# Sheet1.net
KiCad netlist of a schematic drawn in Altium Designer
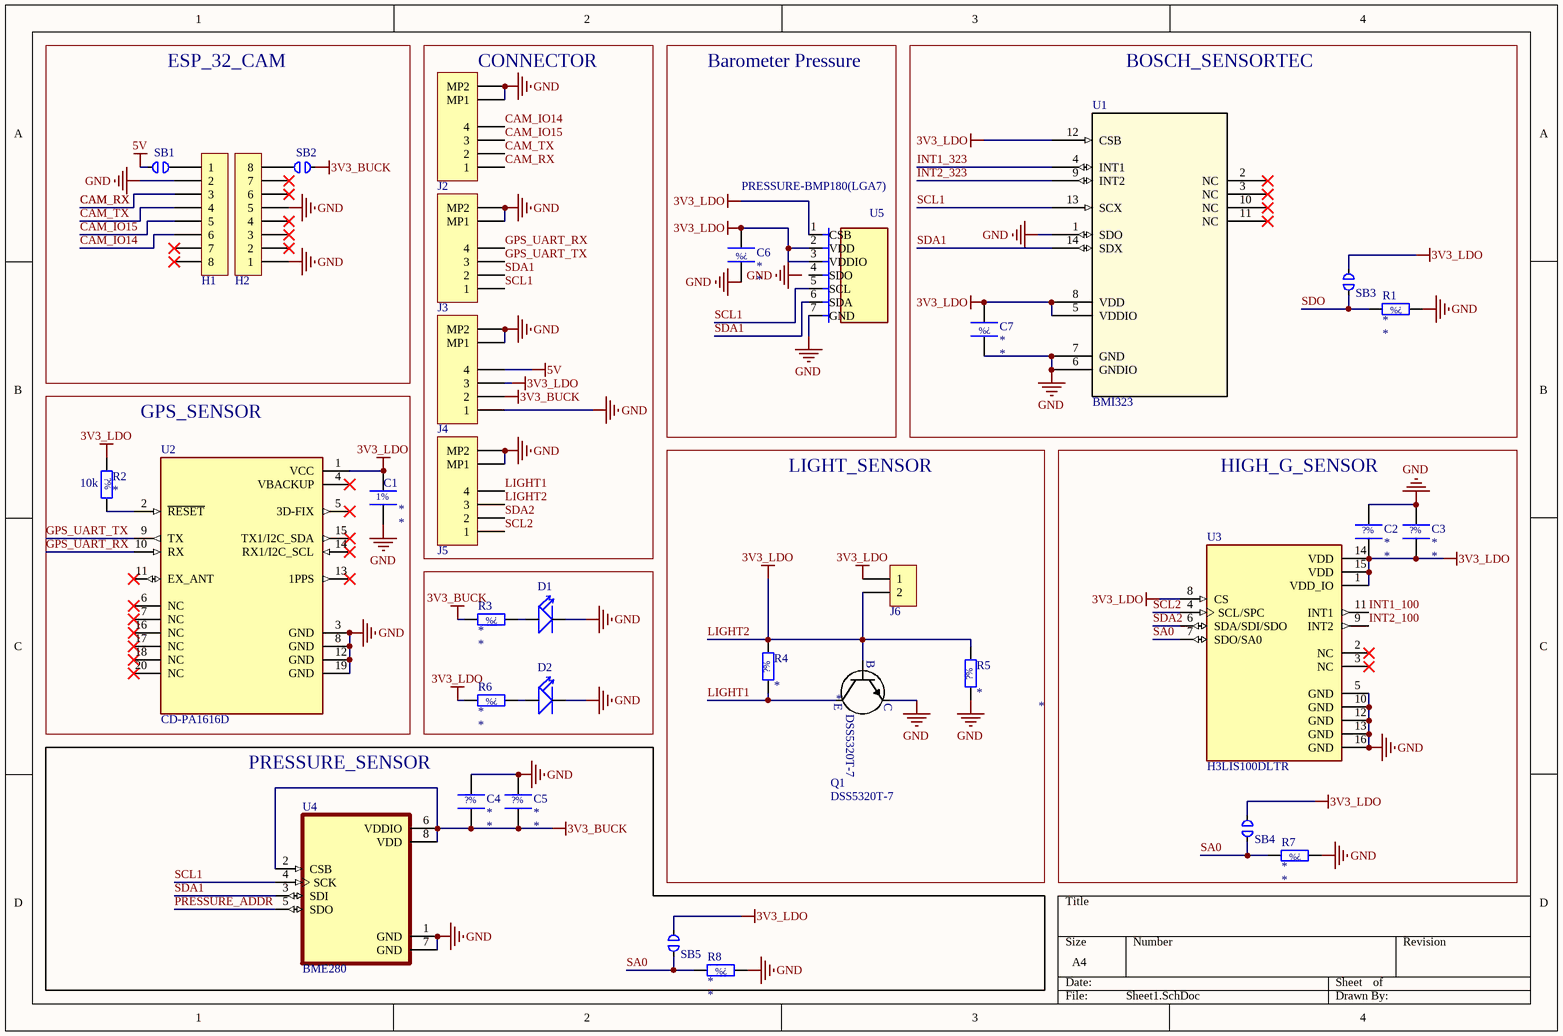
[diagram p0: Sheet1.SchDoc]

(export (version "E")
  (design (tool "Eeschema 10.0.6"))
  (components
    (comp (ref "C1")
      (value "*")
      (footprint "CAPACITOR_0805_2012M-70N")
      (description "Passive - Capacitor, Generic")
      (fields
        (field (name "TOLERANCE") "1%")
        (field (name "MF PART NO.") "*")
        (field (name "ALTIUM_VALUE") "*")
      )
      (libsource (lib "APSS Generic Components") (part "Generic Capacitor"))
    )
    (comp (ref "C2")
      (value "*")
      (footprint "CAPACITOR_0805_2012M-70N")
      (description "Passive - Capacitor, Generic")
      (fields
        (field (name "TOLERANCE") "?%")
        (field (name "MF PART NO.") "*")
        (field (name "ALTIUM_VALUE") "*")
      )
      (libsource (lib "APSS Generic Components") (part "Generic Capacitor"))
    )
    (comp (ref "C3")
      (value "*")
      (footprint "CAPACITOR_0805_2012M-70N")
      (description "Passive - Capacitor, Generic")
      (fields
        (field (name "TOLERANCE") "?%")
        (field (name "MF PART NO.") "*")
        (field (name "ALTIUM_VALUE") "*")
      )
      (libsource (lib "APSS Generic Components") (part "Generic Capacitor"))
    )
    (comp (ref "C4")
      (value "*")
      (footprint "CAPACITOR_0805_2012M-70N")
      (description "Passive - Capacitor, Generic")
      (fields
        (field (name "TOLERANCE") "?%")
        (field (name "MF PART NO.") "*")
        (field (name "ALTIUM_VALUE") "*")
      )
      (libsource (lib "APSS Generic Components") (part "Generic Capacitor"))
    )
    (comp (ref "C5")
      (value "*")
      (footprint "CAPACITOR_0805_2012M-70N")
      (description "Passive - Capacitor, Generic")
      (fields
        (field (name "TOLERANCE") "?%")
        (field (name "MF PART NO.") "*")
        (field (name "ALTIUM_VALUE") "*")
      )
      (libsource (lib "APSS Generic Components") (part "Generic Capacitor"))
    )
    (comp (ref "C6")
      (value "*")
      (footprint "CAPACITOR_0805_2012M-70N")
      (description "Passive - Capacitor, Generic")
      (fields
        (field (name "TOLERANCE") "?%")
        (field (name "MF PART NO.") "*")
        (field (name "ALTIUM_VALUE") "*")
      )
      (libsource (lib "") (part "Generic Capacitor_1"))
    )
    (comp (ref "C7")
      (value "*")
      (footprint "CAPACITOR_0805_2012M-70N")
      (description "Passive - Capacitor, Generic")
      (fields
        (field (name "TOLERANCE") "?%")
        (field (name "MF PART NO.") "*")
        (field (name "ALTIUM_VALUE") "*")
      )
      (libsource (lib "") (part "Generic Capacitor_1"))
    )
    (comp (ref "D1")
      (value "LED-SMD-RED-DIFFUSED(0603)")
      (footprint "LED-0603")
      (description "Red - LED Indication - Discrete 1.95V 0603 (1608 Metric)")
      (fields (field (name "MF") "Everlight Electronics") (field (name "MP") "19-217/R6C-AL1M2VY/3T"))
      (libsource (lib "Custom_schematic") (part "LED-SMD-RED-DIFFUSED(0603)"))
    )
    (comp (ref "D2")
      (value "LED-SMD-RED-DIFFUSED(0603)")
      (footprint "LED-0603")
      (description "Red - LED Indication - Discrete 1.95V 0603 (1608 Metric)")
      (fields (field (name "MF") "Everlight Electronics") (field (name "MP") "19-217/R6C-AL1M2VY/3T"))
      (libsource (lib "Custom_schematic") (part "LED-SMD-RED-DIFFUSED(0603)"))
    )
    (comp (ref "H1")
      (value "HDR,2.54mm,1x8")
      (footprint "APSS Connectors:HEADER_2.54MM_1x8PIN")
      (description "Connector - 2.54mm, 1x8-pin")
      (libsource (lib "") (part "HDR,2.54mm,1x8_1"))
    )
    (comp (ref "H2")
      (value "HDR,2.54mm,1x8")
      (footprint "APSS Connectors:HEADER_2.54MM_1x8PIN")
      (description "Connector - 2.54mm, 1x8-pin")
      (libsource (lib "APSS Connectors") (part "HDR,2.54mm,1x8"))
    )
    (comp (ref "J2")
      (value "0533980471")
      (footprint "APSS Connectors:MOLEX_0533980471")
      (description "Connector - Picoblade 04-pin, SMT, STR")
      (fields (field (name "APSS STANDARD PART") "APSS Standard"))
      (libsource (lib "APSS Connectors") (part "0533980471"))
    )
    (comp (ref "J3")
      (value "0533980471")
      (footprint "APSS Connectors:MOLEX_0533980471")
      (description "Connector - Picoblade 04-pin, SMT, STR")
      (fields (field (name "APSS STANDARD PART") "APSS Standard"))
      (libsource (lib "APSS Connectors") (part "0533980471"))
    )
    (comp (ref "J4")
      (value "0533980471")
      (footprint "APSS Connectors:MOLEX_0533980471")
      (description "Connector - Picoblade 04-pin, SMT, STR")
      (fields (field (name "APSS STANDARD PART") "APSS Standard"))
      (libsource (lib "APSS Connectors") (part "0533980471"))
    )
    (comp (ref "J5")
      (value "0533980471")
      (footprint "APSS Connectors:MOLEX_0533980471")
      (description "Connector - Picoblade 04-pin, SMT, STR")
      (fields (field (name "APSS STANDARD PART") "APSS Standard"))
      (libsource (lib "APSS Connectors") (part "0533980471"))
    )
    (comp (ref "J6")
      (value "0530470210")
      (footprint "APSS Connectors:MOLEX_0530470210")
      (description "Connector - Picoblade 02-pin, TH, STR")
      (fields (field (name "APSS STANDARD PART") "APSS Standard"))
      (libsource (lib "APSS Connectors") (part "0530470210"))
    )
    (comp (ref "Q1")
      (value "DSS5320T-7")
      (footprint "APSS Prototype Parts:SOT23-3N-1.15mm")
      (description "Transistor - BJT PNP DSS5320T-7")
      (fields (field (name "POWER") "600mW") (field (name "APSS STANDARD PART") "APSS Standard"))
      (libsource (lib "APSS Prototype Parts") (part "DSS5320T-7"))
    )
    (comp (ref "R1")
      (value "*")
      (footprint "RESISTOR_0805_2012M-50N")
      (description "Passive - Resistor, Generic")
      (fields
        (field (name "TOLERANCE") "?%")
        (field (name "MF PART NO.") "*")
        (field (name "ALTIUM_VALUE") "*")
      )
      (libsource (lib "APSS Generic Components") (part "Generic Resistor"))
    )
    (comp (ref "R2")
      (value "5=Value")
      (footprint "RESISTOR_0805_2012M-50N")
      (description "Passive - Resistor, Generic")
      (fields (field (name "TOLERANCE") "?%") (field (name "MF PART NO.") "*") (field (name "R1") "10k"))
      (libsource (lib "") (part "Generic Resistor_1"))
    )
    (comp (ref "R3")
      (value "*")
      (footprint "RESISTOR_0805_2012M-50N")
      (description "Passive - Resistor, Generic")
      (fields
        (field (name "TOLERANCE") "?%")
        (field (name "MF PART NO.") "*")
        (field (name "ALTIUM_VALUE") "*")
      )
      (libsource (lib "APSS Generic Components") (part "Generic Resistor"))
    )
    (comp (ref "R4")
      (value "*")
      (footprint "RESISTOR_0805_2012M-50N")
      (description "Passive - Resistor, Generic")
      (fields
        (field (name "TOLERANCE") "?%")
        (field (name "MF PART NO.") "*")
        (field (name "ALTIUM_VALUE") "*")
      )
      (libsource (lib "") (part "Generic Resistor_2"))
    )
    (comp (ref "R5")
      (value "*")
      (footprint "RESISTOR_0805_2012M-50N")
      (description "Passive - Resistor, Generic")
      (fields
        (field (name "TOLERANCE") "?%")
        (field (name "MF PART NO.") "*")
        (field (name "ALTIUM_VALUE") "*")
      )
      (libsource (lib "") (part "Generic Resistor_2"))
    )
    (comp (ref "R6")
      (value "*")
      (footprint "RESISTOR_0805_2012M-50N")
      (description "Passive - Resistor, Generic")
      (fields
        (field (name "TOLERANCE") "?%")
        (field (name "MF PART NO.") "*")
        (field (name "ALTIUM_VALUE") "*")
      )
      (libsource (lib "APSS Generic Components") (part "Generic Resistor"))
    )
    (comp (ref "R7")
      (value "*")
      (footprint "RESISTOR_0805_2012M-50N")
      (description "Passive - Resistor, Generic")
      (fields
        (field (name "TOLERANCE") "?%")
        (field (name "MF PART NO.") "*")
        (field (name "ALTIUM_VALUE") "*")
      )
      (libsource (lib "APSS Generic Components") (part "Generic Resistor"))
    )
    (comp (ref "R8")
      (value "*")
      (footprint "RESISTOR_0805_2012M-50N")
      (description "Passive - Resistor, Generic")
      (fields
        (field (name "TOLERANCE") "?%")
        (field (name "MF PART NO.") "*")
        (field (name "ALTIUM_VALUE") "*")
      )
      (libsource (lib "APSS Generic Components") (part "Generic Resistor"))
    )
    (comp (ref "SB1")
      (value "Solder Jumper Normally Open")
      (footprint "APSS Generic Components:Solder bridge Chevron 0603 Open")
      (libsource (lib "APSS Generic Components") (part "Solder Jumper Normally Open"))
    )
    (comp (ref "SB2")
      (value "Solder Jumper Normally Open")
      (footprint "APSS Generic Components:Solder bridge Chevron 0603 Open")
      (libsource (lib "APSS Generic Components") (part "Solder Jumper Normally Open"))
    )
    (comp (ref "SB3")
      (value "Solder Jumper Normally Open")
      (footprint "APSS Generic Components:Solder bridge Chevron 0603 Open")
      (libsource (lib "APSS Generic Components") (part "Solder Jumper Normally Open"))
    )
    (comp (ref "SB4")
      (value "Solder Jumper Normally Open")
      (footprint "APSS Generic Components:Solder bridge Chevron 0603 Open")
      (libsource (lib "APSS Generic Components") (part "Solder Jumper Normally Open"))
    )
    (comp (ref "SB5")
      (value "Solder Jumper Normally Open")
      (footprint "APSS Generic Components:Solder bridge Chevron 0603 Open")
      (libsource (lib "APSS Generic Components") (part "Solder Jumper Normally Open"))
    )
    (comp (ref "U1")
      (value "BMI323")
      (footprint "BMI323_BOS")
      (description "Description")
      (fields (field (name "COPYRIGHT") "Copyright (C) 2026 Ultra Librarian. All rights reserved."))
      (libsource (lib "Custom_schematic") (part "BMI323"))
    )
    (comp (ref "U2")
      (value "CD-PA1616D")
      (footprint "XCVR_CD-PA1616D")
      (description "CD-PA1616DGNSS patch antenna module")
      (fields (field (name "MF") "CD Top"))
      (libsource (lib "Custom_schematic") (part "CD-PA1616D"))
    )
    (comp (ref "U3")
      (value "H3LIS100DLTR")
      (footprint "PQFN50P300X300X100-16N")
      (description "Accelerometer X, Y, Z Axis Â±100g 25Hz ~ 200Hz 16-TFLGA (3x3)")
      (fields (field (name "MF") "STMicroelectronics"))
      (libsource (lib "Custom_schematic") (part "H3LIS100DLTR"))
    )
    (comp (ref "U4")
      (value "BME280")
      (footprint "PSON65P250X250X100-8N")
      (description "Board Mount Humidity Sensors MEMS humidity, pressure and temperature sensor")
      (fields (field (name "MF") "Bosch"))
      (libsource (lib "Custom_schematic") (part "BME280"))
    )
    (comp (ref "U5")
      (value "PRESSURE-BMP180(LGA7)")
      (footprint "LGA7-1.5-3.8X3.6MM")
      (description "Pressure Sensor 4.35PSI ~ 15.95PSI (30kPa ~ 110kPa) Absolute - 16 ~ 19 b 7-VLGA")
      (fields (field (name "MF") "Bosch") (field (name "MP") "BMP180"))
      (libsource (lib "Custom_schematic") (part "PRESSURE-BMP180(LGA7)"))
    )
  )
  (nets
    (net (code "1") (name "/CAM_IO14") (class "Default")
      (node (ref "H1") (pin "6") (pinfunction "6_6") (pintype "passive"))
      (node (ref "J2") (pin "4") (pinfunction "4_4") (pintype "passive"))
    )
    (net (code "2") (name "/CAM_IO15") (class "Default")
      (node (ref "H1") (pin "5") (pinfunction "5_5") (pintype "passive"))
      (node (ref "J2") (pin "3") (pinfunction "3_3") (pintype "passive"))
    )
    (net (code "3") (name "/CAM_RX") (class "Default")
      (node (ref "H1") (pin "3") (pinfunction "3_3") (pintype "passive"))
      (node (ref "J2") (pin "1") (pinfunction "1_1") (pintype "passive"))
    )
    (net (code "4") (name "/CAM_TX") (class "Default")
      (node (ref "H1") (pin "4") (pinfunction "4_4") (pintype "passive"))
      (node (ref "J2") (pin "2") (pinfunction "2_2") (pintype "passive"))
    )
    (net (code "5") (name "/GPS_UART_RX") (class "Default")
      (node (ref "J3") (pin "4") (pinfunction "4_4") (pintype "passive"))
      (node (ref "U2") (pin "10") (pinfunction "RX_10") (pintype "input"))
    )
    (net (code "6") (name "/GPS_UART_TX") (class "Default")
      (node (ref "J3") (pin "3") (pinfunction "3_3") (pintype "passive"))
      (node (ref "U2") (pin "9") (pinfunction "TX_9") (pintype "output"))
    )
    (net (code "7") (name "/INT1_100") (class "Default")
      (node (ref "U3") (pin "11") (pinfunction "INT1_11") (pintype "output"))
    )
    (net (code "8") (name "/INT1_323") (class "Default")
      (node (ref "U1") (pin "4") (pinfunction "INT1_4") (pintype "bidirectional"))
    )
    (net (code "9") (name "/INT2_100") (class "Default")
      (node (ref "U3") (pin "9") (pinfunction "INT2_9") (pintype "output"))
    )
    (net (code "10") (name "/INT2_323") (class "Default")
      (node (ref "U1") (pin "9") (pinfunction "INT2_9") (pintype "bidirectional"))
    )
    (net (code "11") (name "/LIGHT1") (class "Default")
      (node (ref "J5") (pin "4") (pinfunction "4_4") (pintype "passive"))
      (node (ref "Q1") (pin "2") (pinfunction "E_2") (pintype "passive"))
      (node (ref "R4") (pin "1") (pinfunction "1_1") (pintype "passive"))
    )
    (net (code "12") (name "/PRESSURE_ADDR") (class "Default")
      (node (ref "U4") (pin "5") (pinfunction "SDO_5") (pintype "bidirectional"))
    )
    (net (code "13") (name "/SA0") (class "Default")
      (node (ref "R7") (pin "2") (pinfunction "2_2") (pintype "passive"))
      (node (ref "R8") (pin "2") (pinfunction "2_2") (pintype "passive"))
      (node (ref "SB4") (pin "1") (pinfunction "1_1") (pintype "passive"))
      (node (ref "SB5") (pin "1") (pinfunction "1_1") (pintype "passive"))
      (node (ref "U3") (pin "7") (pinfunction "SDO/SA0_7") (pintype "bidirectional"))
    )
    (net (code "14") (name "/SCL1") (class "Default")
      (node (ref "J3") (pin "1") (pinfunction "1_1") (pintype "passive"))
      (node (ref "U1") (pin "13") (pinfunction "SCX_13") (pintype "input"))
      (node (ref "U4") (pin "4") (pinfunction "SCK_4") (pintype "input"))
      (node (ref "U5") (pin "5") (pinfunction "SCL_5") (pintype "bidirectional"))
    )
    (net (code "15") (name "/SCL2") (class "Default")
      (node (ref "J5") (pin "1") (pinfunction "1_1") (pintype "passive"))
      (node (ref "U3") (pin "4") (pinfunction "SCL/SPC_4") (pintype "input"))
    )
    (net (code "16") (name "/SDA1") (class "Default")
      (node (ref "J3") (pin "2") (pinfunction "2_2") (pintype "passive"))
      (node (ref "U1") (pin "14") (pinfunction "SDX_14") (pintype "bidirectional"))
      (node (ref "U4") (pin "3") (pinfunction "SDI_3") (pintype "bidirectional"))
      (node (ref "U5") (pin "6") (pinfunction "SDA_6") (pintype "bidirectional"))
    )
    (net (code "17") (name "/SDA2") (class "Default")
      (node (ref "J5") (pin "2") (pinfunction "2_2") (pintype "passive"))
      (node (ref "U3") (pin "6") (pinfunction "SDA/SDI/SDO_6") (pintype "bidirectional"))
    )
    (net (code "18") (name "/SDO") (class "Default")
      (node (ref "R1") (pin "2") (pinfunction "2_2") (pintype "passive"))
      (node (ref "SB3") (pin "1") (pinfunction "1_1") (pintype "passive"))
    )
    (net (code "19") (name "3V3_BUCK") (class "Default")
      (node (ref "C4") (pin "1") (pinfunction "1_1") (pintype "passive"))
      (node (ref "C5") (pin "1") (pinfunction "1_1") (pintype "passive"))
      (node (ref "J4") (pin "2") (pinfunction "2_2") (pintype "passive"))
      (node (ref "R3") (pin "2") (pinfunction "2_2") (pintype "passive"))
      (node (ref "SB2") (pin "2") (pinfunction "2_2") (pintype "passive"))
      (node (ref "U4") (pin "2") (pinfunction "CSB_2") (pintype "input"))
      (node (ref "U4") (pin "6") (pinfunction "VDDIO_6") (pintype "power_in"))
      (node (ref "U4") (pin "8") (pinfunction "VDD_8") (pintype "power_in"))
    )
    (net (code "20") (name "3V3_LDO") (class "Default")
      (node (ref "C1") (pin "2") (pinfunction "2_2") (pintype "passive"))
      (node (ref "C2") (pin "1") (pinfunction "1_1") (pintype "passive"))
      (node (ref "C3") (pin "1") (pinfunction "1_1") (pintype "passive"))
      (node (ref "C6") (pin "1") (pinfunction "1_1") (pintype "passive"))
      (node (ref "C7") (pin "1") (pinfunction "1_1") (pintype "passive"))
      (node (ref "J4") (pin "3") (pinfunction "3_3") (pintype "passive"))
      (node (ref "J5") (pin "3") (pinfunction "3_3") (pintype "passive"))
      (node (ref "J6") (pin "1") (pinfunction "1_1") (pintype "passive"))
      (node (ref "J6") (pin "2") (pinfunction "2_2") (pintype "passive"))
      (node (ref "Q1") (pin "1") (pinfunction "B_1") (pintype "passive"))
      (node (ref "R2") (pin "1") (pinfunction "1_1") (pintype "passive"))
      (node (ref "R4") (pin "2") (pinfunction "2_2") (pintype "passive"))
      (node (ref "R5") (pin "2") (pinfunction "2_2") (pintype "passive"))
      (node (ref "R6") (pin "2") (pinfunction "2_2") (pintype "passive"))
      (node (ref "SB3") (pin "2") (pinfunction "2_2") (pintype "passive"))
      (node (ref "SB4") (pin "2") (pinfunction "2_2") (pintype "passive"))
      (node (ref "SB5") (pin "2") (pinfunction "2_2") (pintype "passive"))
      (node (ref "U1") (pin "12") (pinfunction "CSB_12") (pintype "input"))
      (node (ref "U1") (pin "5") (pinfunction "VDDIO_5") (pintype "power_in"))
      (node (ref "U1") (pin "8") (pinfunction "VDD_8") (pintype "power_in"))
      (node (ref "U2") (pin "1") (pinfunction "VCC_1") (pintype "power_in"))
      (node (ref "U3") (pin "1") (pinfunction "VDD_IO_1") (pintype "power_in"))
      (node (ref "U3") (pin "14") (pinfunction "VDD_14") (pintype "power_in"))
      (node (ref "U3") (pin "15") (pinfunction "VDD_15") (pintype "power_in"))
      (node (ref "U3") (pin "8") (pinfunction "CS_8") (pintype "input"))
      (node (ref "U5") (pin "1") (pinfunction "CSB_1") (pintype "bidirectional"))
      (node (ref "U5") (pin "2") (pinfunction "VDD_2") (pintype "bidirectional"))
      (node (ref "U5") (pin "3") (pinfunction "VDDIO_3") (pintype "bidirectional"))
    )
    (net (code "21") (name "5V") (class "Default")
      (node (ref "J4") (pin "4") (pinfunction "4_4") (pintype "passive"))
      (node (ref "SB1") (pin "1") (pinfunction "1_1") (pintype "passive"))
    )
    (net (code "22") (name "GND") (class "Default")
      (node (ref "C1") (pin "1") (pinfunction "1_1") (pintype "passive"))
      (node (ref "C2") (pin "2") (pinfunction "2_2") (pintype "passive"))
      (node (ref "C3") (pin "2") (pinfunction "2_2") (pintype "passive"))
      (node (ref "C4") (pin "2") (pinfunction "2_2") (pintype "passive"))
      (node (ref "C5") (pin "2") (pinfunction "2_2") (pintype "passive"))
      (node (ref "C6") (pin "2") (pinfunction "2_2") (pintype "passive"))
      (node (ref "C7") (pin "2") (pinfunction "2_2") (pintype "passive"))
      (node (ref "D1") (pin "NEG") (pinfunction "NEG_NEG") (pintype "passive"))
      (node (ref "D2") (pin "NEG") (pinfunction "NEG_NEG") (pintype "passive"))
      (node (ref "H1") (pin "2") (pinfunction "2_2") (pintype "passive"))
      (node (ref "H2") (pin "1") (pinfunction "1_1") (pintype "passive"))
      (node (ref "H2") (pin "5") (pinfunction "5_5") (pintype "passive"))
      (node (ref "J2") (pin "MP1") (pinfunction "MP1_MP1") (pintype "passive"))
      (node (ref "J2") (pin "MP2") (pinfunction "MP2_MP2") (pintype "passive"))
      (node (ref "J3") (pin "MP1") (pinfunction "MP1_MP1") (pintype "passive"))
      (node (ref "J3") (pin "MP2") (pinfunction "MP2_MP2") (pintype "passive"))
      (node (ref "J4") (pin "1") (pinfunction "1_1") (pintype "passive"))
      (node (ref "J4") (pin "MP1") (pinfunction "MP1_MP1") (pintype "passive"))
      (node (ref "J4") (pin "MP2") (pinfunction "MP2_MP2") (pintype "passive"))
      (node (ref "J5") (pin "MP1") (pinfunction "MP1_MP1") (pintype "passive"))
      (node (ref "J5") (pin "MP2") (pinfunction "MP2_MP2") (pintype "passive"))
      (node (ref "Q1") (pin "3") (pinfunction "C_3") (pintype "passive"))
      (node (ref "R1") (pin "1") (pinfunction "1_1") (pintype "passive"))
      (node (ref "R5") (pin "1") (pinfunction "1_1") (pintype "passive"))
      (node (ref "R7") (pin "1") (pinfunction "1_1") (pintype "passive"))
      (node (ref "R8") (pin "1") (pinfunction "1_1") (pintype "passive"))
      (node (ref "U1") (pin "1") (pinfunction "SDO_1") (pintype "bidirectional"))
      (node (ref "U1") (pin "6") (pinfunction "GNDIO_6") (pintype "power_in"))
      (node (ref "U1") (pin "7") (pinfunction "GND_7") (pintype "power_in"))
      (node (ref "U2") (pin "12") (pinfunction "GND_12") (pintype "power_in"))
      (node (ref "U2") (pin "19") (pinfunction "GND_19") (pintype "power_in"))
      (node (ref "U2") (pin "3") (pinfunction "GND_3") (pintype "power_in"))
      (node (ref "U2") (pin "8") (pinfunction "GND_8") (pintype "power_in"))
      (node (ref "U3") (pin "10") (pinfunction "GND_10") (pintype "power_in"))
      (node (ref "U3") (pin "12") (pinfunction "GND_12") (pintype "power_in"))
      (node (ref "U3") (pin "13") (pinfunction "GND_13") (pintype "power_in"))
      (node (ref "U3") (pin "16") (pinfunction "GND_16") (pintype "power_in"))
      (node (ref "U3") (pin "5") (pinfunction "GND_5") (pintype "power_in"))
      (node (ref "U4") (pin "1") (pinfunction "GND_1") (pintype "power_in"))
      (node (ref "U4") (pin "7") (pinfunction "GND_7") (pintype "power_in"))
      (node (ref "U5") (pin "7") (pinfunction "GND_7") (pintype "bidirectional"))
    )
    (net (code "23") (name "Net-(D1-PadPOS)") (class "Default")
      (node (ref "D1") (pin "POS") (pinfunction "POS_POS") (pintype "passive"))
      (node (ref "R3") (pin "1") (pinfunction "1_1") (pintype "passive"))
    )
    (net (code "24") (name "Net-(D2-PadPOS)") (class "Default")
      (node (ref "D2") (pin "POS") (pinfunction "POS_POS") (pintype "passive"))
      (node (ref "R6") (pin "1") (pinfunction "1_1") (pintype "passive"))
    )
    (net (code "25") (name "Net-(H1-Pad1)") (class "Default")
      (node (ref "H1") (pin "1") (pinfunction "1_1") (pintype "passive"))
      (node (ref "SB1") (pin "2") (pinfunction "2_2") (pintype "passive"))
    )
    (net (code "26") (name "Net-(H2-Pad8)") (class "Default")
      (node (ref "H2") (pin "8") (pinfunction "8_8") (pintype "passive"))
      (node (ref "SB2") (pin "1") (pinfunction "1_1") (pintype "passive"))
    )
    (net (code "27") (name "Net-(U2-~{RESET})") (class "Default")
      (node (ref "R2") (pin "2") (pinfunction "2_2") (pintype "passive"))
      (node (ref "U2") (pin "2") (pinfunction "~{RESET}_2") (pintype "input"))
    )
    (net (code "28") (name "unconnected-(H1-Pad7)") (class "Default")
      (node (ref "H1") (pin "7") (pinfunction "7_7") (pintype "passive+no_connect"))
    )
    (net (code "29") (name "unconnected-(H1-Pad8)") (class "Default")
      (node (ref "H1") (pin "8") (pinfunction "8_8") (pintype "passive+no_connect"))
    )
    (net (code "30") (name "unconnected-(H2-Pad2)") (class "Default")
      (node (ref "H2") (pin "2") (pinfunction "2_2") (pintype "passive+no_connect"))
    )
    (net (code "31") (name "unconnected-(H2-Pad3)") (class "Default")
      (node (ref "H2") (pin "3") (pinfunction "3_3") (pintype "passive+no_connect"))
    )
    (net (code "32") (name "unconnected-(H2-Pad4)") (class "Default")
      (node (ref "H2") (pin "4") (pinfunction "4_4") (pintype "passive+no_connect"))
    )
    (net (code "33") (name "unconnected-(H2-Pad6)") (class "Default")
      (node (ref "H2") (pin "6") (pinfunction "6_6") (pintype "passive+no_connect"))
    )
    (net (code "34") (name "unconnected-(H2-Pad7)") (class "Default")
      (node (ref "H2") (pin "7") (pinfunction "7_7") (pintype "passive+no_connect"))
    )
    (net (code "35") (name "unconnected-(U1-NC-Pad2)") (class "Default")
      (node (ref "U1") (pin "2") (pinfunction "NC_2") (pintype "passive+no_connect"))
    )
    (net (code "36") (name "unconnected-(U1-NC-Pad3)") (class "Default")
      (node (ref "U1") (pin "3") (pinfunction "NC_3") (pintype "passive+no_connect"))
    )
    (net (code "37") (name "unconnected-(U1-NC-Pad10)") (class "Default")
      (node (ref "U1") (pin "10") (pinfunction "NC_10") (pintype "passive+no_connect"))
    )
    (net (code "38") (name "unconnected-(U1-NC-Pad11)") (class "Default")
      (node (ref "U1") (pin "11") (pinfunction "NC_11") (pintype "passive+no_connect"))
    )
    (net (code "39") (name "unconnected-(U2-1PPS-Pad13)") (class "Default")
      (node (ref "U2") (pin "13") (pinfunction "1PPS_13") (pintype "output+no_connect"))
    )
    (net (code "40") (name "unconnected-(U2-3D-FIX-Pad5)") (class "Default")
      (node (ref "U2") (pin "5") (pinfunction "3D-FIX_5") (pintype "output+no_connect"))
    )
    (net (code "41") (name "unconnected-(U2-EX_ANT-Pad11)") (class "Default")
      (node (ref "U2") (pin "11") (pinfunction "EX_ANT_11") (pintype "bidirectional+no_connect"))
    )
    (net (code "42") (name "unconnected-(U2-NC-Pad6)") (class "Default")
      (node (ref "U2") (pin "6") (pinfunction "NC_6") (pintype "passive+no_connect"))
    )
    (net (code "43") (name "unconnected-(U2-NC-Pad7)") (class "Default")
      (node (ref "U2") (pin "7") (pinfunction "NC_7") (pintype "passive+no_connect"))
    )
    (net (code "44") (name "unconnected-(U2-NC-Pad16)") (class "Default")
      (node (ref "U2") (pin "16") (pinfunction "NC_16") (pintype "passive+no_connect"))
    )
    (net (code "45") (name "unconnected-(U2-NC-Pad17)") (class "Default")
      (node (ref "U2") (pin "17") (pinfunction "NC_17") (pintype "passive+no_connect"))
    )
    (net (code "46") (name "unconnected-(U2-NC-Pad18)") (class "Default")
      (node (ref "U2") (pin "18") (pinfunction "NC_18") (pintype "passive+no_connect"))
    )
    (net (code "47") (name "unconnected-(U2-NC-Pad20)") (class "Default")
      (node (ref "U2") (pin "20") (pinfunction "NC_20") (pintype "passive+no_connect"))
    )
    (net (code "48") (name "unconnected-(U2-RX1{slash}I2C_SCL-Pad14)") (class "Default")
      (node (ref "U2") (pin "14") (pinfunction "RX1/I2C_SCL_14") (pintype "input+no_connect"))
    )
    (net (code "49") (name "unconnected-(U2-TX1{slash}I2C_SDA-Pad15)") (class "Default")
      (node (ref "U2") (pin "15") (pinfunction "TX1/I2C_SDA_15") (pintype "output+no_connect"))
    )
    (net (code "50") (name "unconnected-(U2-VBACKUP-Pad4)") (class "Default")
      (node (ref "U2") (pin "4") (pinfunction "VBACKUP_4") (pintype "power_in+no_connect"))
    )
    (net (code "51") (name "unconnected-(U3-NC-Pad2)") (class "Default")
      (node (ref "U3") (pin "2") (pinfunction "NC_2") (pintype "passive+no_connect"))
    )
    (net (code "52") (name "unconnected-(U3-NC-Pad3)") (class "Default")
      (node (ref "U3") (pin "3") (pinfunction "NC_3") (pintype "passive+no_connect"))
    )
    (net (code "53") (name "unconnected-(U5-SDO-Pad4)") (class "Default")
      (node (ref "U5") (pin "4") (pinfunction "SDO_4") (pintype "bidirectional"))
    )
  )
)
